# DRV8301_2.net
KiCad netlist of a schematic drawn in Altium Designer
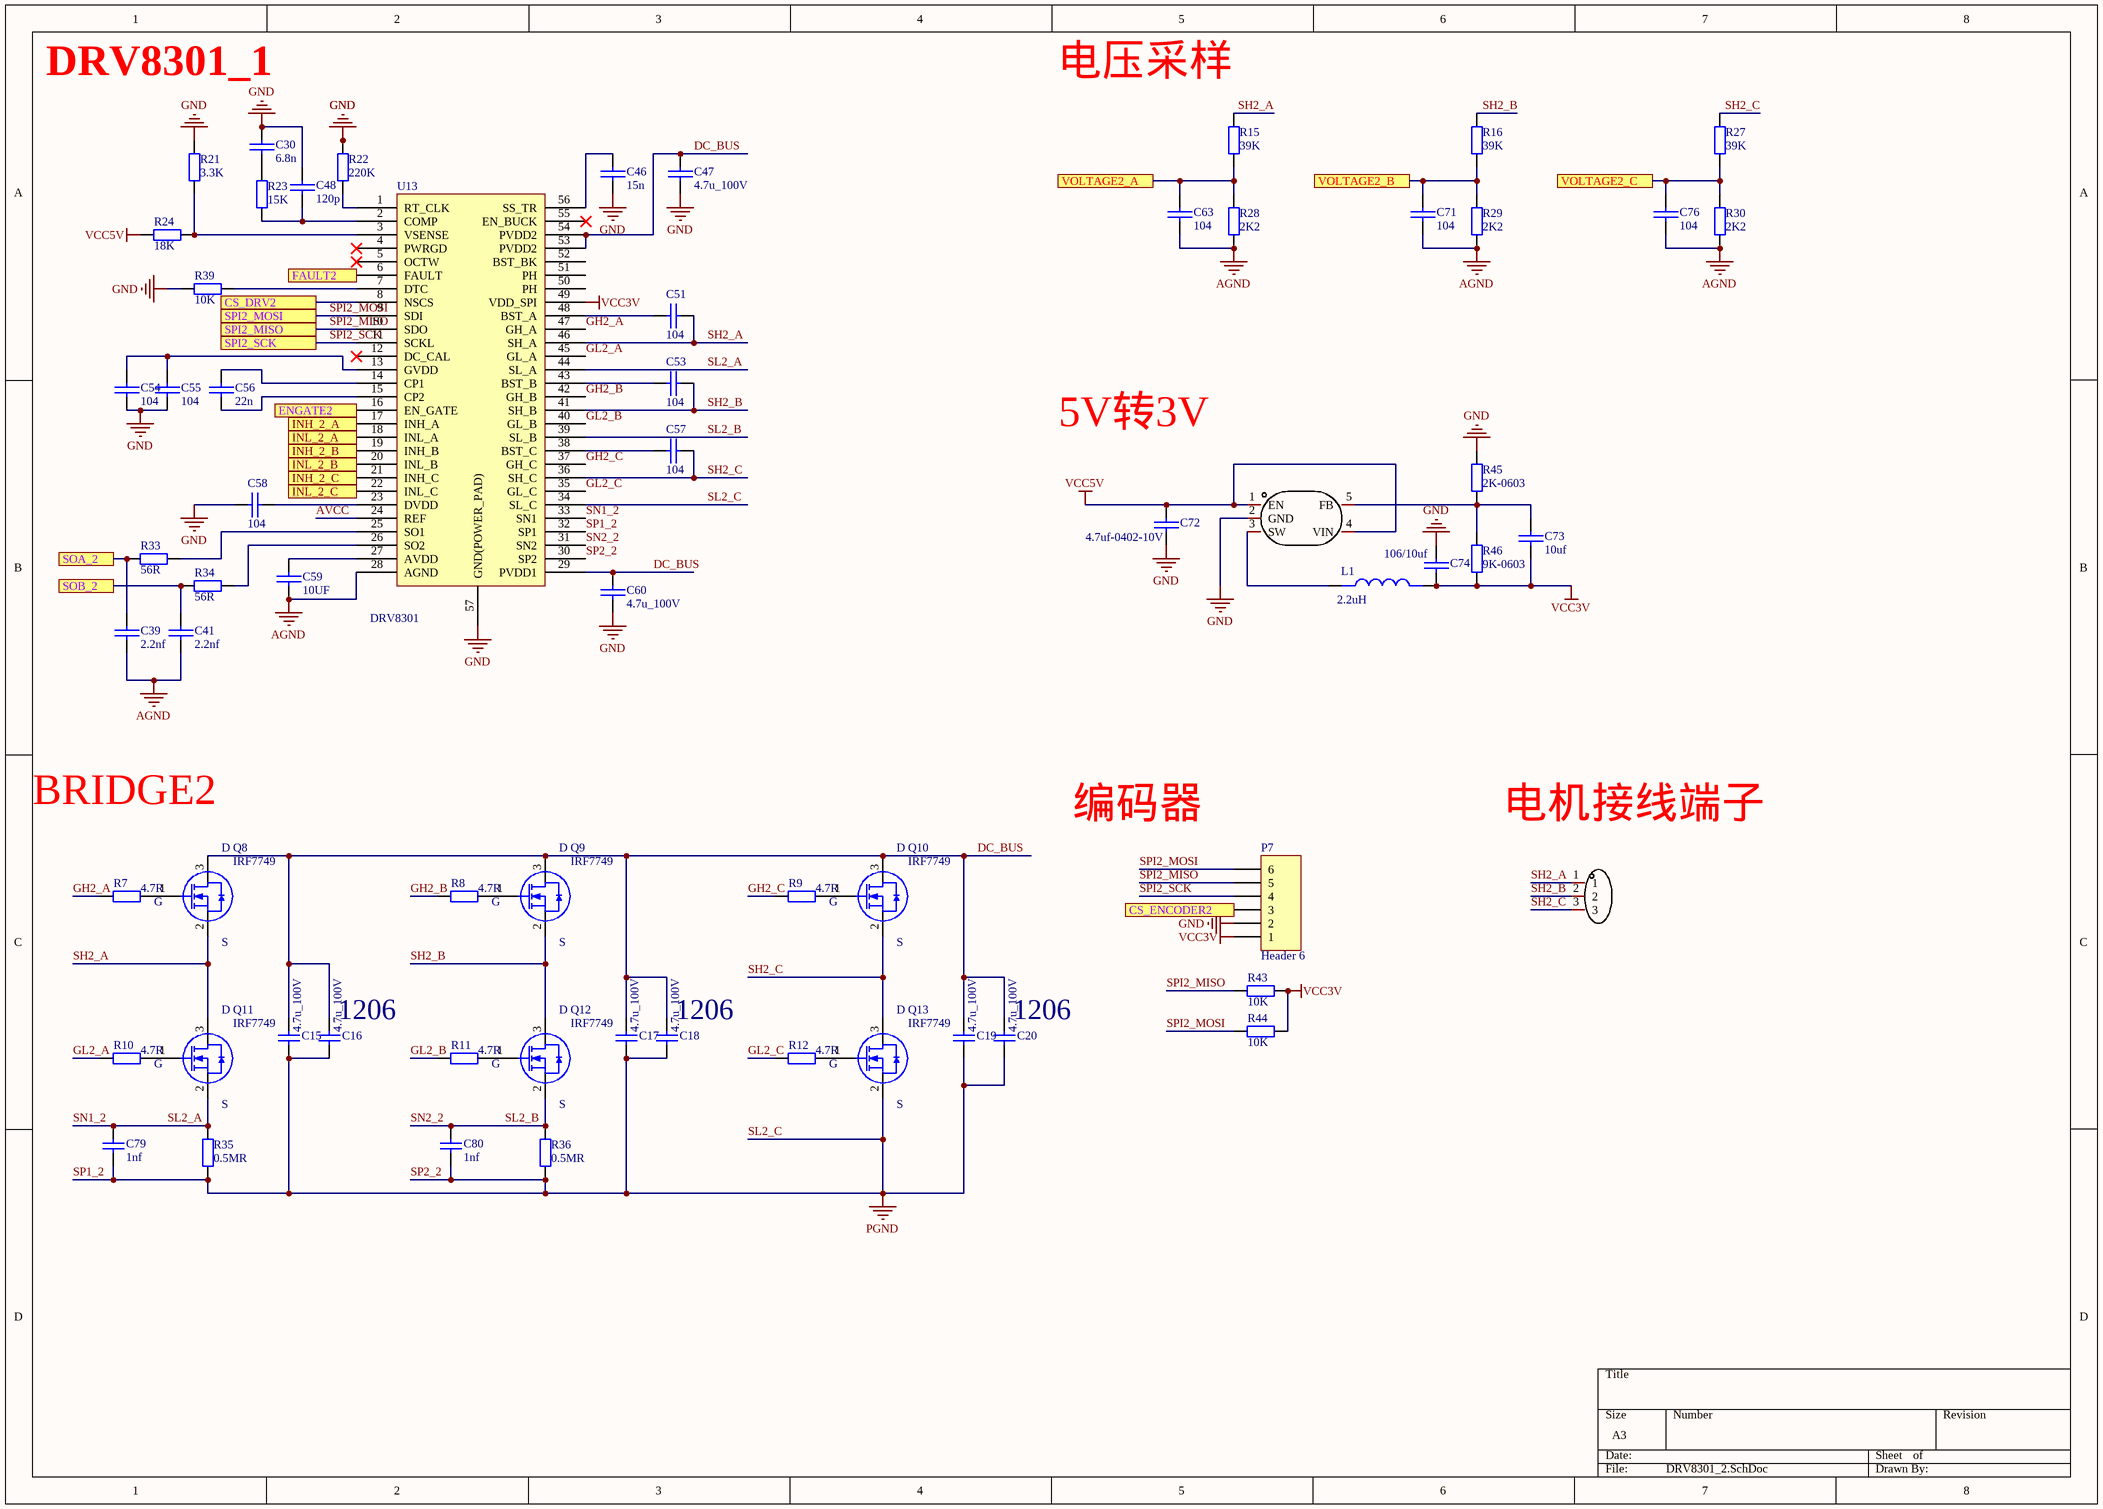
[diagram p0: DRV8301_2.SchDoc]

(export (version "E")
  (design (tool "Eeschema 10.0.6"))
  (components
    (comp (ref "C15")
      (value "4.7u_100V")
      (footprint "1206_C")
      (description "无极性电容")
      (fields (field (name "Comment") "Cap") (field (name "PUBLISHER") "Altium Limited"))
      (libsource (lib "Panel_Point") (part "Cap_6"))
    )
    (comp (ref "C16")
      (value "4.7u_100V")
      (footprint "1206_C")
      (description "无极性电容")
      (fields (field (name "Comment") "Cap") (field (name "PUBLISHER") "Altium Limited"))
      (libsource (lib "Panel_Point") (part "Cap_6"))
    )
    (comp (ref "C17")
      (value "4.7u_100V")
      (footprint "1206_C")
      (description "无极性电容")
      (fields (field (name "Comment") "Cap") (field (name "PUBLISHER") "Altium Limited"))
      (libsource (lib "Panel_Point") (part "Cap_6"))
    )
    (comp (ref "C18")
      (value "4.7u_100V")
      (footprint "1206_C")
      (description "无极性电容")
      (fields (field (name "Comment") "Cap") (field (name "PUBLISHER") "Altium Limited"))
      (libsource (lib "Panel_Point") (part "Cap_6"))
    )
    (comp (ref "C19")
      (value "4.7u_100V")
      (footprint "1206_C")
      (description "无极性电容")
      (fields (field (name "Comment") "Cap") (field (name "PUBLISHER") "Altium Limited"))
      (libsource (lib "Panel_Point") (part "Cap_6"))
    )
    (comp (ref "C20")
      (value "4.7u_100V")
      (footprint "1206_C")
      (description "无极性电容")
      (fields (field (name "Comment") "Cap") (field (name "PUBLISHER") "Altium Limited"))
      (libsource (lib "Panel_Point") (part "Cap_6"))
    )
    (comp (ref "C30")
      (value "6.8n")
      (footprint "0402C")
      (fields (field (name "Comment") "CAP"))
      (libsource (lib "MY SCH LIB__JCH") (part "CAP"))
    )
    (comp (ref "C39")
      (value "2.2nf")
      (footprint "0402C")
      (fields (field (name "Comment") "CAP"))
      (libsource (lib "MY SCH LIB__JCH") (part "CAP"))
    )
    (comp (ref "C41")
      (value "2.2nf")
      (footprint "0402C")
      (fields (field (name "Comment") "CAP"))
      (libsource (lib "MY SCH LIB__JCH") (part "CAP"))
    )
    (comp (ref "C46")
      (value "15n")
      (footprint "0402C")
      (fields (field (name "Comment") "CAP"))
      (libsource (lib "MY SCH LIB__JCH") (part "CAP"))
    )
    (comp (ref "C47")
      (value "4.7u_100V")
      (footprint "0603_C")
      (fields (field (name "Comment") "CAP"))
      (libsource (lib "MY SCH LIB__JCH") (part "CAP"))
    )
    (comp (ref "C48")
      (value "120p")
      (footprint "0402C")
      (fields (field (name "Comment") "CAP"))
      (libsource (lib "MY SCH LIB__JCH") (part "CAP"))
    )
    (comp (ref "C51")
      (value "104")
      (footprint "0402C")
      (fields (field (name "Comment") "CAP"))
      (libsource (lib "MY SCH LIB__JCH") (part "CAP"))
    )
    (comp (ref "C53")
      (value "104")
      (footprint "0402C")
      (fields (field (name "Comment") "CAP"))
      (libsource (lib "MY SCH LIB__JCH") (part "CAP"))
    )
    (comp (ref "C54")
      (value "104")
      (footprint "0402C")
      (fields (field (name "Comment") "CAP"))
      (libsource (lib "MY SCH LIB__JCH") (part "CAP"))
    )
    (comp (ref "C55")
      (value "104")
      (footprint "0402C")
      (fields (field (name "Comment") "CAP"))
      (libsource (lib "MY SCH LIB__JCH") (part "CAP"))
    )
    (comp (ref "C56")
      (value "22n")
      (footprint "0402C")
      (fields (field (name "Comment") "CAP"))
      (libsource (lib "MY SCH LIB__JCH") (part "CAP"))
    )
    (comp (ref "C57")
      (value "104")
      (footprint "0402C")
      (fields (field (name "Comment") "CAP"))
      (libsource (lib "MY SCH LIB__JCH") (part "CAP"))
    )
    (comp (ref "C58")
      (value "104")
      (footprint "0402C")
      (fields (field (name "Comment") "CAP"))
      (libsource (lib "MY SCH LIB__JCH") (part "CAP"))
    )
    (comp (ref "C59")
      (value "10UF")
      (footprint "0402C")
      (fields (field (name "Comment") "CAP"))
      (libsource (lib "MY SCH LIB__JCH") (part "CAP"))
    )
    (comp (ref "C60")
      (value "4.7u_100V")
      (footprint "0603_C")
      (fields (field (name "Comment") "CAP"))
      (libsource (lib "MY SCH LIB__JCH") (part "CAP"))
    )
    (comp (ref "C63")
      (value "104")
      (footprint "0402C")
      (fields (field (name "Comment") "CAP"))
      (libsource (lib "MY SCH LIB__JCH") (part "CAP"))
    )
    (comp (ref "C71")
      (value "104")
      (footprint "0402C")
      (fields (field (name "Comment") "CAP"))
      (libsource (lib "MY SCH LIB__JCH") (part "CAP"))
    )
    (comp (ref "C72")
      (value "4.7uf-0402-10V")
      (footprint "0402C")
      (fields (field (name "Comment") "CAP"))
      (libsource (lib "MY SCH LIB") (part "CAP"))
    )
    (comp (ref "C73")
      (value "10uf")
      (footprint "0402C")
      (fields (field (name "Comment") "CAP"))
      (libsource (lib "MY SCH LIB") (part "CAP"))
    )
    (comp (ref "C74")
      (value "106/10uf")
      (footprint "0402C")
      (fields (field (name "Comment") "CAP"))
      (libsource (lib "MY SCH LIB") (part "CAP"))
    )
    (comp (ref "C76")
      (value "104")
      (footprint "0402C")
      (fields (field (name "Comment") "CAP"))
      (libsource (lib "MY SCH LIB__JCH") (part "CAP"))
    )
    (comp (ref "C79")
      (value "1nf")
      (footprint "0402C")
      (description "无极性电容")
      (fields (field (name "Comment") "Cap") (field (name "PUBLISHER") "Altium Limited"))
      (libsource (lib "Panel_Point") (part "Cap_6"))
    )
    (comp (ref "C80")
      (value "1nf")
      (footprint "0402C")
      (description "无极性电容")
      (fields (field (name "Comment") "Cap") (field (name "PUBLISHER") "Altium Limited"))
      (libsource (lib "Panel_Point") (part "Cap_6"))
    )
    (comp (ref "L1")
      (value "2.2uH")
      (footprint "IND-SMD_L4.4-W4.2")
      (libsource (lib "Panel_Point") (part "IND"))
    )
    (comp (ref "P7")
      (value "Header 6")
      (footprint "A1002WR-S-6P")
      (description "Header, 6-Pin")
      (fields (field (name "PUBLISHER") "Altium Limited"))
      (libsource (lib "FOC") (part "Header 6"))
    )
    (comp (ref "Q8")
      (value "IRF7749")
      (footprint "IRF7480")
      (description "MOS(场效应管)")
      (libsource (lib "FOC") (part "IRF7749"))
    )
    (comp (ref "Q9")
      (value "IRF7749")
      (footprint "IRF7480")
      (description "MOS(场效应管)")
      (libsource (lib "FOC") (part "IRF7749"))
    )
    (comp (ref "Q10")
      (value "IRF7749")
      (footprint "IRF7480")
      (description "MOS(场效应管)")
      (libsource (lib "FOC") (part "IRF7749"))
    )
    (comp (ref "Q11")
      (value "IRF7749")
      (footprint "IRF7480")
      (description "MOS(场效应管)")
      (libsource (lib "FOC") (part "IRF7749"))
    )
    (comp (ref "Q12")
      (value "IRF7749")
      (footprint "IRF7480")
      (description "MOS(场效应管)")
      (libsource (lib "FOC") (part "IRF7749"))
    )
    (comp (ref "Q13")
      (value "IRF7749")
      (footprint "IRF7480")
      (description "MOS(场效应管)")
      (libsource (lib "FOC") (part "IRF7749"))
    )
    (comp (ref "R7")
      (value "4.7R")
      (footprint "0402R")
      (description "贴片电阻")
      (fields (field (name "Comment") "Res1") (field (name "PUBLISHER") "Altium Limited"))
      (libsource (lib "") (part "Res1_1"))
    )
    (comp (ref "R8")
      (value "4.7R")
      (footprint "0402R")
      (description "贴片电阻")
      (fields (field (name "Comment") "Res1") (field (name "PUBLISHER") "Altium Limited"))
      (libsource (lib "") (part "Res1_1"))
    )
    (comp (ref "R9")
      (value "4.7R")
      (footprint "0402R")
      (description "贴片电阻")
      (fields (field (name "Comment") "Res1") (field (name "PUBLISHER") "Altium Limited"))
      (libsource (lib "") (part "Res1_1"))
    )
    (comp (ref "R10")
      (value "4.7R")
      (footprint "0402R")
      (description "贴片电阻")
      (fields (field (name "Comment") "Res1") (field (name "PUBLISHER") "Altium Limited"))
      (libsource (lib "") (part "Res1_1"))
    )
    (comp (ref "R11")
      (value "4.7R")
      (footprint "0402R")
      (description "贴片电阻")
      (fields (field (name "Comment") "Res1") (field (name "PUBLISHER") "Altium Limited"))
      (libsource (lib "") (part "Res1_1"))
    )
    (comp (ref "R12")
      (value "4.7R")
      (footprint "0402R")
      (description "贴片电阻")
      (fields (field (name "Comment") "Res1") (field (name "PUBLISHER") "Altium Limited"))
      (libsource (lib "") (part "Res1_1"))
    )
    (comp (ref "R15")
      (value "39K")
      (footprint "0402R")
      (description "Resistor")
      (fields (field (name "PUBLISHER") "Altium Limited"))
      (libsource (lib "") (part "Res2_2"))
    )
    (comp (ref "R16")
      (value "39K")
      (footprint "0402R")
      (description "Resistor")
      (fields (field (name "PUBLISHER") "Altium Limited"))
      (libsource (lib "") (part "Res2_2"))
    )
    (comp (ref "R21")
      (value "3.3K")
      (footprint "0402R")
      (description "Resistor")
      (fields (field (name "PUBLISHER") "Altium Limited"))
      (libsource (lib "") (part "Res2_2"))
    )
    (comp (ref "R22")
      (value "220K")
      (footprint "0402R")
      (description "Resistor")
      (fields (field (name "PUBLISHER") "Altium Limited"))
      (libsource (lib "") (part "Res2_2"))
    )
    (comp (ref "R23")
      (value "15K")
      (footprint "0402R")
      (description "Resistor")
      (fields (field (name "PUBLISHER") "Altium Limited"))
      (libsource (lib "") (part "Res2_2"))
    )
    (comp (ref "R24")
      (value "18K")
      (footprint "0402R")
      (description "Resistor")
      (fields (field (name "PUBLISHER") "Altium Limited"))
      (libsource (lib "Miscellaneous Devices") (part "Res2"))
    )
    (comp (ref "R27")
      (value "39K")
      (footprint "0402R")
      (description "Resistor")
      (fields (field (name "PUBLISHER") "Altium Limited"))
      (libsource (lib "") (part "Res2_2"))
    )
    (comp (ref "R28")
      (value "2K2")
      (footprint "0402R")
      (description "Resistor")
      (fields (field (name "PUBLISHER") "Altium Limited"))
      (libsource (lib "") (part "Res2_1"))
    )
    (comp (ref "R29")
      (value "2K2")
      (footprint "0402R")
      (description "Resistor")
      (fields (field (name "PUBLISHER") "Altium Limited"))
      (libsource (lib "") (part "Res2_1"))
    )
    (comp (ref "R30")
      (value "2K2")
      (footprint "0402R")
      (description "Resistor")
      (fields (field (name "PUBLISHER") "Altium Limited"))
      (libsource (lib "") (part "Res2_1"))
    )
    (comp (ref "R33")
      (value "56R")
      (footprint "0402R")
      (description "Resistor")
      (fields (field (name "PUBLISHER") "Altium Limited"))
      (libsource (lib "Miscellaneous Devices") (part "Res2"))
    )
    (comp (ref "R34")
      (value "56R")
      (footprint "0402R")
      (description "Resistor")
      (fields (field (name "PUBLISHER") "Altium Limited"))
      (libsource (lib "Miscellaneous Devices") (part "Res2"))
    )
    (comp (ref "R35")
      (value "0.5MR")
      (footprint "0.5mr_6W")
      (description "贴片电阻")
      (fields (field (name "Comment") "Res1") (field (name "PUBLISHER") "Altium Limited"))
      (libsource (lib "SMC_Devices") (part "Res1"))
    )
    (comp (ref "R36")
      (value "0.5MR")
      (footprint "0.5mr_6W")
      (description "贴片电阻")
      (fields (field (name "Comment") "Res1") (field (name "PUBLISHER") "Altium Limited"))
      (libsource (lib "SMC_Devices") (part "Res1"))
    )
    (comp (ref "R39")
      (value "10K")
      (footprint "0402R")
      (description "Resistor")
      (fields (field (name "PUBLISHER") "Altium Limited"))
      (libsource (lib "Miscellaneous Devices") (part "Res2"))
    )
    (comp (ref "R43")
      (value "10K")
      (footprint "0402R")
      (description "Resistor")
      (fields (field (name "PUBLISHER") "Altium Limited"))
      (libsource (lib "Miscellaneous Devices") (part "Res2"))
    )
    (comp (ref "R44")
      (value "10K")
      (footprint "0402R")
      (description "Resistor")
      (fields (field (name "PUBLISHER") "Altium Limited"))
      (libsource (lib "Miscellaneous Devices") (part "Res2"))
    )
    (comp (ref "R45")
      (value "2K-0603")
      (footprint "0603_R")
      (description "Resistor")
      (fields (field (name "PUBLISHER") "Altium Limited"))
      (libsource (lib "") (part "Res2_1"))
    )
    (comp (ref "R46")
      (value "9K-0603")
      (footprint "0603_R")
      (description "Resistor")
      (fields (field (name "PUBLISHER") "Altium Limited"))
      (libsource (lib "") (part "Res2_1"))
    )
    (comp (ref "U8")
      (value "MR30-M")
      (footprint "MR30-M-SMD")
      (fields (field (name "MANUFACTURER") "AMASS(艾迈斯)"))
      (libsource (lib "FOC") (part "MR30-M"))
    )
    (comp (ref "U11")
      (value "TLV62569DBVR")
      (footprint "SOT-23-5_L3.0-W1.7-P0.95-LS2.8-BR")
      (fields (field (name "MANUFACTURER") "TI(德州仪器)"))
      (libsource (lib "FOC") (part "TLV62569DBVR"))
    )
    (comp (ref "U13")
      (value "DRV8301")
      (footprint "HTSSOP-56_L14.0-W6.0-P0.50-LS8.0-BL")
      (description "三相整流桥芯片")
      (libsource (lib "FOC") (part "DRV8301"))
    )
  )
  (nets
    (net (code "1") (name "/AVCC") (class "Default")
      (node (ref "U13") (pin "24") (pinfunction "REF_24") (pintype "passive"))
    )
    (net (code "2") (name "/CS_DRV2") (class "Default")
      (node (ref "U13") (pin "8") (pinfunction "NSCS_8") (pintype "passive"))
    )
    (net (code "3") (name "/CS_ENCODER2") (class "Default")
      (node (ref "P7") (pin "3") (pinfunction "3_3") (pintype "passive"))
    )
    (net (code "4") (name "/DC_BUS") (class "Default")
      (node (ref "C15") (pin "2") (pinfunction "2_2") (pintype "passive"))
      (node (ref "C16") (pin "2") (pinfunction "2_2") (pintype "passive"))
      (node (ref "C17") (pin "2") (pinfunction "2_2") (pintype "passive"))
      (node (ref "C18") (pin "2") (pinfunction "2_2") (pintype "passive"))
      (node (ref "C19") (pin "2") (pinfunction "2_2") (pintype "passive"))
      (node (ref "C20") (pin "2") (pinfunction "2_2") (pintype "passive"))
      (node (ref "C47") (pin "2") (pinfunction "2_2") (pintype "passive"))
      (node (ref "C60") (pin "2") (pinfunction "2_2") (pintype "passive"))
      (node (ref "Q10") (pin "3") (pinfunction "D_3") (pintype "passive"))
      (node (ref "Q8") (pin "3") (pinfunction "D_3") (pintype "passive"))
      (node (ref "Q9") (pin "3") (pinfunction "D_3") (pintype "passive"))
      (node (ref "U13") (pin "29") (pinfunction "PVDD1_29") (pintype "passive"))
      (node (ref "U13") (pin "53") (pinfunction "PVDD2_53") (pintype "passive"))
      (node (ref "U13") (pin "54") (pinfunction "PVDD2_54") (pintype "passive"))
    )
    (net (code "5") (name "/ENGATE2") (class "Default")
      (node (ref "U13") (pin "16") (pinfunction "EN_GATE_16") (pintype "passive"))
    )
    (net (code "6") (name "/FAULT2") (class "Default")
      (node (ref "U13") (pin "6") (pinfunction "FAULT_6") (pintype "passive"))
    )
    (net (code "7") (name "/GH2_A") (class "Default")
      (node (ref "R7") (pin "1") (pinfunction "1_1") (pintype "passive"))
      (node (ref "U13") (pin "47") (pinfunction "GH_A_47") (pintype "passive"))
    )
    (net (code "8") (name "/GH2_B") (class "Default")
      (node (ref "R8") (pin "1") (pinfunction "1_1") (pintype "passive"))
      (node (ref "U13") (pin "42") (pinfunction "GH_B_42") (pintype "passive"))
    )
    (net (code "9") (name "/GH2_C") (class "Default")
      (node (ref "R9") (pin "1") (pinfunction "1_1") (pintype "passive"))
      (node (ref "U13") (pin "37") (pinfunction "GH_C_37") (pintype "passive"))
    )
    (net (code "10") (name "/GL2_A") (class "Default")
      (node (ref "R10") (pin "1") (pinfunction "1_1") (pintype "passive"))
      (node (ref "U13") (pin "45") (pinfunction "GL_A_45") (pintype "passive"))
    )
    (net (code "11") (name "/GL2_B") (class "Default")
      (node (ref "R11") (pin "1") (pinfunction "1_1") (pintype "passive"))
      (node (ref "U13") (pin "40") (pinfunction "GL_B_40") (pintype "passive"))
    )
    (net (code "12") (name "/GL2_C") (class "Default")
      (node (ref "R12") (pin "1") (pinfunction "1_1") (pintype "passive"))
      (node (ref "U13") (pin "35") (pinfunction "GL_C_35") (pintype "passive"))
    )
    (net (code "13") (name "/INH_2_A") (class "Default")
      (node (ref "U13") (pin "17") (pinfunction "INH_A_17") (pintype "passive"))
    )
    (net (code "14") (name "/INH_2_B") (class "Default")
      (node (ref "U13") (pin "19") (pinfunction "INH_B_19") (pintype "passive"))
    )
    (net (code "15") (name "/INH_2_C") (class "Default")
      (node (ref "U13") (pin "21") (pinfunction "INH_C_21") (pintype "passive"))
    )
    (net (code "16") (name "/INL_2_A") (class "Default")
      (node (ref "U13") (pin "18") (pinfunction "INL_A_18") (pintype "passive"))
    )
    (net (code "17") (name "/INL_2_B") (class "Default")
      (node (ref "U13") (pin "20") (pinfunction "INL_B_20") (pintype "passive"))
    )
    (net (code "18") (name "/INL_2_C") (class "Default")
      (node (ref "U13") (pin "22") (pinfunction "INL_C_22") (pintype "passive"))
    )
    (net (code "19") (name "/SH2_A") (class "Default")
      (node (ref "C51") (pin "1") (pinfunction "1_1") (pintype "passive"))
      (node (ref "Q11") (pin "3") (pinfunction "D_3") (pintype "passive"))
      (node (ref "Q8") (pin "2") (pinfunction "S_2") (pintype "passive"))
      (node (ref "R15") (pin "2") (pinfunction "2_2") (pintype "passive"))
      (node (ref "U13") (pin "46") (pinfunction "SH_A_46") (pintype "passive"))
      (node (ref "U8") (pin "1") (pinfunction "1_1") (pintype "passive"))
    )
    (net (code "20") (name "/SH2_B") (class "Default")
      (node (ref "C53") (pin "1") (pinfunction "1_1") (pintype "passive"))
      (node (ref "Q12") (pin "3") (pinfunction "D_3") (pintype "passive"))
      (node (ref "Q9") (pin "2") (pinfunction "S_2") (pintype "passive"))
      (node (ref "R16") (pin "2") (pinfunction "2_2") (pintype "passive"))
      (node (ref "U13") (pin "41") (pinfunction "SH_B_41") (pintype "passive"))
      (node (ref "U8") (pin "2") (pinfunction "2_2") (pintype "passive"))
    )
    (net (code "21") (name "/SH2_C") (class "Default")
      (node (ref "C57") (pin "1") (pinfunction "1_1") (pintype "passive"))
      (node (ref "Q10") (pin "2") (pinfunction "S_2") (pintype "passive"))
      (node (ref "Q13") (pin "3") (pinfunction "D_3") (pintype "passive"))
      (node (ref "R27") (pin "2") (pinfunction "2_2") (pintype "passive"))
      (node (ref "U13") (pin "36") (pinfunction "SH_C_36") (pintype "passive"))
      (node (ref "U8") (pin "3") (pinfunction "3_3") (pintype "passive"))
    )
    (net (code "22") (name "/SL2_A") (class "Default")
      (node (ref "C79") (pin "2") (pinfunction "2_2") (pintype "passive"))
      (node (ref "Q11") (pin "2") (pinfunction "S_2") (pintype "passive"))
      (node (ref "R35") (pin "2") (pinfunction "2_2") (pintype "passive"))
      (node (ref "U13") (pin "33") (pinfunction "SN1_33") (pintype "passive"))
      (node (ref "U13") (pin "44") (pinfunction "SL_A_44") (pintype "passive"))
    )
    (net (code "23") (name "/SL2_B") (class "Default")
      (node (ref "C80") (pin "2") (pinfunction "2_2") (pintype "passive"))
      (node (ref "Q12") (pin "2") (pinfunction "S_2") (pintype "passive"))
      (node (ref "R36") (pin "2") (pinfunction "2_2") (pintype "passive"))
      (node (ref "U13") (pin "31") (pinfunction "SN2_31") (pintype "passive"))
      (node (ref "U13") (pin "39") (pinfunction "SL_B_39") (pintype "passive"))
    )
    (net (code "24") (name "/SOA_2") (class "Default")
      (node (ref "C39") (pin "2") (pinfunction "2_2") (pintype "passive"))
      (node (ref "R33") (pin "1") (pinfunction "1_1") (pintype "passive"))
    )
    (net (code "25") (name "/SOB_2") (class "Default")
      (node (ref "C41") (pin "2") (pinfunction "2_2") (pintype "passive"))
      (node (ref "R34") (pin "1") (pinfunction "1_1") (pintype "passive"))
    )
    (net (code "26") (name "/SPI2_MISO") (class "Default")
      (node (ref "P7") (pin "5") (pinfunction "5_5") (pintype "passive"))
      (node (ref "R43") (pin "1") (pinfunction "1_1") (pintype "passive"))
      (node (ref "U13") (pin "10") (pinfunction "SDO_10") (pintype "passive"))
    )
    (net (code "27") (name "/SPI2_MOSI") (class "Default")
      (node (ref "P7") (pin "6") (pinfunction "6_6") (pintype "passive"))
      (node (ref "R44") (pin "1") (pinfunction "1_1") (pintype "passive"))
      (node (ref "U13") (pin "9") (pinfunction "SDI_9") (pintype "passive"))
    )
    (net (code "28") (name "/SPI2_SCK") (class "Default")
      (node (ref "P7") (pin "4") (pinfunction "4_4") (pintype "passive"))
      (node (ref "U13") (pin "11") (pinfunction "SCKL_11") (pintype "passive"))
    )
    (net (code "29") (name "/VOLTAGE2_A") (class "Default")
      (node (ref "C63") (pin "1") (pinfunction "1_1") (pintype "passive"))
      (node (ref "R15") (pin "1") (pinfunction "1_1") (pintype "passive"))
      (node (ref "R28") (pin "1") (pinfunction "1_1") (pintype "passive"))
    )
    (net (code "30") (name "/VOLTAGE2_B") (class "Default")
      (node (ref "C71") (pin "1") (pinfunction "1_1") (pintype "passive"))
      (node (ref "R16") (pin "1") (pinfunction "1_1") (pintype "passive"))
      (node (ref "R29") (pin "1") (pinfunction "1_1") (pintype "passive"))
    )
    (net (code "31") (name "/VOLTAGE2_C") (class "Default")
      (node (ref "C76") (pin "1") (pinfunction "1_1") (pintype "passive"))
      (node (ref "R27") (pin "1") (pinfunction "1_1") (pintype "passive"))
      (node (ref "R30") (pin "1") (pinfunction "1_1") (pintype "passive"))
    )
    (net (code "32") (name "AGND") (class "Default")
      (node (ref "C39") (pin "1") (pinfunction "1_1") (pintype "passive"))
      (node (ref "C41") (pin "1") (pinfunction "1_1") (pintype "passive"))
      (node (ref "C59") (pin "1") (pinfunction "1_1") (pintype "passive"))
      (node (ref "C63") (pin "2") (pinfunction "2_2") (pintype "passive"))
      (node (ref "C71") (pin "2") (pinfunction "2_2") (pintype "passive"))
      (node (ref "C76") (pin "2") (pinfunction "2_2") (pintype "passive"))
      (node (ref "R28") (pin "2") (pinfunction "2_2") (pintype "passive"))
      (node (ref "R29") (pin "2") (pinfunction "2_2") (pintype "passive"))
      (node (ref "R30") (pin "2") (pinfunction "2_2") (pintype "passive"))
      (node (ref "U13") (pin "28") (pinfunction "AGND_28") (pintype "passive"))
    )
    (net (code "33") (name "GND") (class "Default")
      (node (ref "C30") (pin "2") (pinfunction "2_2") (pintype "passive"))
      (node (ref "C46") (pin "1") (pinfunction "1_1") (pintype "passive"))
      (node (ref "C47") (pin "1") (pinfunction "1_1") (pintype "passive"))
      (node (ref "C48") (pin "2") (pinfunction "2_2") (pintype "passive"))
      (node (ref "C54") (pin "1") (pinfunction "1_1") (pintype "passive"))
      (node (ref "C55") (pin "1") (pinfunction "1_1") (pintype "passive"))
      (node (ref "C58") (pin "1") (pinfunction "1_1") (pintype "passive"))
      (node (ref "C60") (pin "1") (pinfunction "1_1") (pintype "passive"))
      (node (ref "C72") (pin "2") (pinfunction "2_2") (pintype "passive"))
      (node (ref "C74") (pin "1") (pinfunction "1_1") (pintype "passive"))
      (node (ref "P7") (pin "2") (pinfunction "2_2") (pintype "passive"))
      (node (ref "R21") (pin "2") (pinfunction "2_2") (pintype "passive"))
      (node (ref "R22") (pin "2") (pinfunction "2_2") (pintype "passive"))
      (node (ref "R39") (pin "1") (pinfunction "1_1") (pintype "passive"))
      (node (ref "R45") (pin "1") (pinfunction "1_1") (pintype "passive"))
      (node (ref "U11") (pin "2") (pinfunction "GND_2") (pintype "passive"))
      (node (ref "U13") (pin "57") (pinfunction "GND(POWER_PAD)_57") (pintype "passive"))
    )
    (net (code "34") (name "Net-(C30-Pad1)") (class "Default")
      (node (ref "C30") (pin "1") (pinfunction "1_1") (pintype "passive"))
      (node (ref "R23") (pin "2") (pinfunction "2_2") (pintype "passive"))
    )
    (net (code "35") (name "Net-(Q8-G)") (class "Default")
      (node (ref "Q8") (pin "1") (pinfunction "G_1") (pintype "passive"))
      (node (ref "R7") (pin "2") (pinfunction "2_2") (pintype "passive"))
    )
    (net (code "36") (name "Net-(Q9-G)") (class "Default")
      (node (ref "Q9") (pin "1") (pinfunction "G_1") (pintype "passive"))
      (node (ref "R8") (pin "2") (pinfunction "2_2") (pintype "passive"))
    )
    (net (code "37") (name "Net-(Q10-G)") (class "Default")
      (node (ref "Q10") (pin "1") (pinfunction "G_1") (pintype "passive"))
      (node (ref "R9") (pin "2") (pinfunction "2_2") (pintype "passive"))
    )
    (net (code "38") (name "Net-(Q11-G)") (class "Default")
      (node (ref "Q11") (pin "1") (pinfunction "G_1") (pintype "passive"))
      (node (ref "R10") (pin "2") (pinfunction "2_2") (pintype "passive"))
    )
    (net (code "39") (name "Net-(Q12-G)") (class "Default")
      (node (ref "Q12") (pin "1") (pinfunction "G_1") (pintype "passive"))
      (node (ref "R11") (pin "2") (pinfunction "2_2") (pintype "passive"))
    )
    (net (code "40") (name "Net-(Q13-G)") (class "Default")
      (node (ref "Q13") (pin "1") (pinfunction "G_1") (pintype "passive"))
      (node (ref "R12") (pin "2") (pinfunction "2_2") (pintype "passive"))
    )
    (net (code "41") (name "Net-(U11-FB)") (class "Default")
      (node (ref "C73") (pin "1") (pinfunction "1_1") (pintype "passive"))
      (node (ref "R45") (pin "2") (pinfunction "2_2") (pintype "passive"))
      (node (ref "R46") (pin "1") (pinfunction "1_1") (pintype "passive"))
      (node (ref "U11") (pin "5") (pinfunction "FB_5") (pintype "passive"))
    )
    (net (code "42") (name "Net-(U11-SW)") (class "Default")
      (node (ref "L1") (pin "1") (pinfunction "Pri-_1") (pintype "passive"))
      (node (ref "U11") (pin "3") (pinfunction "SW_3") (pintype "passive"))
    )
    (net (code "43") (name "Net-(U13-AVDD)") (class "Default")
      (node (ref "C59") (pin "2") (pinfunction "2_2") (pintype "passive"))
      (node (ref "U13") (pin "27") (pinfunction "AVDD_27") (pintype "passive"))
    )
    (net (code "44") (name "Net-(U13-BST_A)") (class "Default")
      (node (ref "C51") (pin "2") (pinfunction "2_2") (pintype "passive"))
      (node (ref "U13") (pin "48") (pinfunction "BST_A_48") (pintype "passive"))
    )
    (net (code "45") (name "Net-(U13-BST_B)") (class "Default")
      (node (ref "C53") (pin "2") (pinfunction "2_2") (pintype "passive"))
      (node (ref "U13") (pin "43") (pinfunction "BST_B_43") (pintype "passive"))
    )
    (net (code "46") (name "Net-(U13-BST_C)") (class "Default")
      (node (ref "C57") (pin "2") (pinfunction "2_2") (pintype "passive"))
      (node (ref "U13") (pin "38") (pinfunction "BST_C_38") (pintype "passive"))
    )
    (net (code "47") (name "Net-(U13-COMP)") (class "Default")
      (node (ref "C48") (pin "1") (pinfunction "1_1") (pintype "passive"))
      (node (ref "R23") (pin "1") (pinfunction "1_1") (pintype "passive"))
      (node (ref "U13") (pin "2") (pinfunction "COMP_2") (pintype "passive"))
    )
    (net (code "48") (name "Net-(U13-CP1)") (class "Default")
      (node (ref "C56") (pin "1") (pinfunction "1_1") (pintype "passive"))
      (node (ref "U13") (pin "14") (pinfunction "CP1_14") (pintype "passive"))
    )
    (net (code "49") (name "Net-(U13-CP2)") (class "Default")
      (node (ref "C56") (pin "2") (pinfunction "2_2") (pintype "passive"))
      (node (ref "U13") (pin "15") (pinfunction "CP2_15") (pintype "passive"))
    )
    (net (code "50") (name "Net-(U13-DTC)") (class "Default")
      (node (ref "R39") (pin "2") (pinfunction "2_2") (pintype "passive"))
      (node (ref "U13") (pin "7") (pinfunction "DTC_7") (pintype "passive"))
    )
    (net (code "51") (name "Net-(U13-DVDD)") (class "Default")
      (node (ref "C58") (pin "2") (pinfunction "2_2") (pintype "passive"))
      (node (ref "U13") (pin "23") (pinfunction "DVDD_23") (pintype "passive"))
    )
    (net (code "52") (name "Net-(U13-GVDD)") (class "Default")
      (node (ref "C54") (pin "2") (pinfunction "2_2") (pintype "passive"))
      (node (ref "C55") (pin "2") (pinfunction "2_2") (pintype "passive"))
      (node (ref "U13") (pin "13") (pinfunction "GVDD_13") (pintype "passive"))
    )
    (net (code "53") (name "Net-(U13-RT_CLK)") (class "Default")
      (node (ref "R22") (pin "1") (pinfunction "1_1") (pintype "passive"))
      (node (ref "U13") (pin "1") (pinfunction "RT_CLK_1") (pintype "passive"))
    )
    (net (code "54") (name "Net-(U13-SO1)") (class "Default")
      (node (ref "R33") (pin "2") (pinfunction "2_2") (pintype "passive"))
      (node (ref "U13") (pin "25") (pinfunction "SO1_25") (pintype "passive"))
    )
    (net (code "55") (name "Net-(U13-SO2)") (class "Default")
      (node (ref "R34") (pin "2") (pinfunction "2_2") (pintype "passive"))
      (node (ref "U13") (pin "26") (pinfunction "SO2_26") (pintype "passive"))
    )
    (net (code "56") (name "Net-(U13-SS_TR)") (class "Default")
      (node (ref "C46") (pin "2") (pinfunction "2_2") (pintype "passive"))
      (node (ref "U13") (pin "56") (pinfunction "SS_TR_56") (pintype "passive"))
    )
    (net (code "57") (name "Net-(U13-VSENSE)") (class "Default")
      (node (ref "R21") (pin "1") (pinfunction "1_1") (pintype "passive"))
      (node (ref "R24") (pin "2") (pinfunction "2_2") (pintype "passive"))
      (node (ref "U13") (pin "3") (pinfunction "VSENSE_3") (pintype "passive"))
    )
    (net (code "58") (name "PGND") (class "Default")
      (node (ref "C15") (pin "1") (pinfunction "1_1") (pintype "passive"))
      (node (ref "C16") (pin "1") (pinfunction "1_1") (pintype "passive"))
      (node (ref "C17") (pin "1") (pinfunction "1_1") (pintype "passive"))
      (node (ref "C18") (pin "1") (pinfunction "1_1") (pintype "passive"))
      (node (ref "C19") (pin "1") (pinfunction "1_1") (pintype "passive"))
      (node (ref "C20") (pin "1") (pinfunction "1_1") (pintype "passive"))
      (node (ref "C79") (pin "1") (pinfunction "1_1") (pintype "passive"))
      (node (ref "C80") (pin "1") (pinfunction "1_1") (pintype "passive"))
      (node (ref "Q13") (pin "2") (pinfunction "S_2") (pintype "passive"))
      (node (ref "R35") (pin "1") (pinfunction "1_1") (pintype "passive"))
      (node (ref "R36") (pin "1") (pinfunction "1_1") (pintype "passive"))
      (node (ref "U13") (pin "30") (pinfunction "SP2_30") (pintype "passive"))
      (node (ref "U13") (pin "32") (pinfunction "SP1_32") (pintype "passive"))
      (node (ref "U13") (pin "34") (pinfunction "SL_C_34") (pintype "passive"))
    )
    (net (code "59") (name "VCC3V") (class "Default")
      (node (ref "C73") (pin "2") (pinfunction "2_2") (pintype "passive"))
      (node (ref "C74") (pin "2") (pinfunction "2_2") (pintype "passive"))
      (node (ref "L1") (pin "2") (pinfunction "Pri-_2") (pintype "passive"))
      (node (ref "P7") (pin "1") (pinfunction "1_1") (pintype "passive"))
      (node (ref "R43") (pin "2") (pinfunction "2_2") (pintype "passive"))
      (node (ref "R44") (pin "2") (pinfunction "2_2") (pintype "passive"))
      (node (ref "R46") (pin "2") (pinfunction "2_2") (pintype "passive"))
      (node (ref "U13") (pin "49") (pinfunction "VDD_SPI_49") (pintype "passive"))
    )
    (net (code "60") (name "VCC5V") (class "Default")
      (node (ref "C72") (pin "1") (pinfunction "1_1") (pintype "passive"))
      (node (ref "R24") (pin "1") (pinfunction "1_1") (pintype "passive"))
      (node (ref "U11") (pin "1") (pinfunction "EN_1") (pintype "passive"))
      (node (ref "U11") (pin "4") (pinfunction "VIN_4") (pintype "passive"))
    )
    (net (code "61") (name "unconnected-(U13-BST_BK-Pad52)") (class "Default")
      (node (ref "U13") (pin "52") (pinfunction "BST_BK_52") (pintype "passive"))
    )
    (net (code "62") (name "unconnected-(U13-DC_CAL-Pad12)") (class "Default")
      (node (ref "U13") (pin "12") (pinfunction "DC_CAL_12") (pintype "passive+no_connect"))
    )
    (net (code "63") (name "unconnected-(U13-EN_BUCK-Pad55)") (class "Default")
      (node (ref "U13") (pin "55") (pinfunction "EN_BUCK_55") (pintype "passive+no_connect"))
    )
    (net (code "64") (name "unconnected-(U13-OCTW-Pad5)") (class "Default")
      (node (ref "U13") (pin "5") (pinfunction "OCTW_5") (pintype "passive+no_connect"))
    )
    (net (code "65") (name "unconnected-(U13-PH-Pad50)") (class "Default")
      (node (ref "U13") (pin "50") (pinfunction "PH_50") (pintype "passive"))
    )
    (net (code "66") (name "unconnected-(U13-PH-Pad51)") (class "Default")
      (node (ref "U13") (pin "51") (pinfunction "PH_51") (pintype "passive"))
    )
    (net (code "67") (name "unconnected-(U13-PWRGD-Pad4)") (class "Default")
      (node (ref "U13") (pin "4") (pinfunction "PWRGD_4") (pintype "passive+no_connect"))
    )
  )
)
